# schematic.net
KiCad netlist of a schematic drawn in Altium Designer
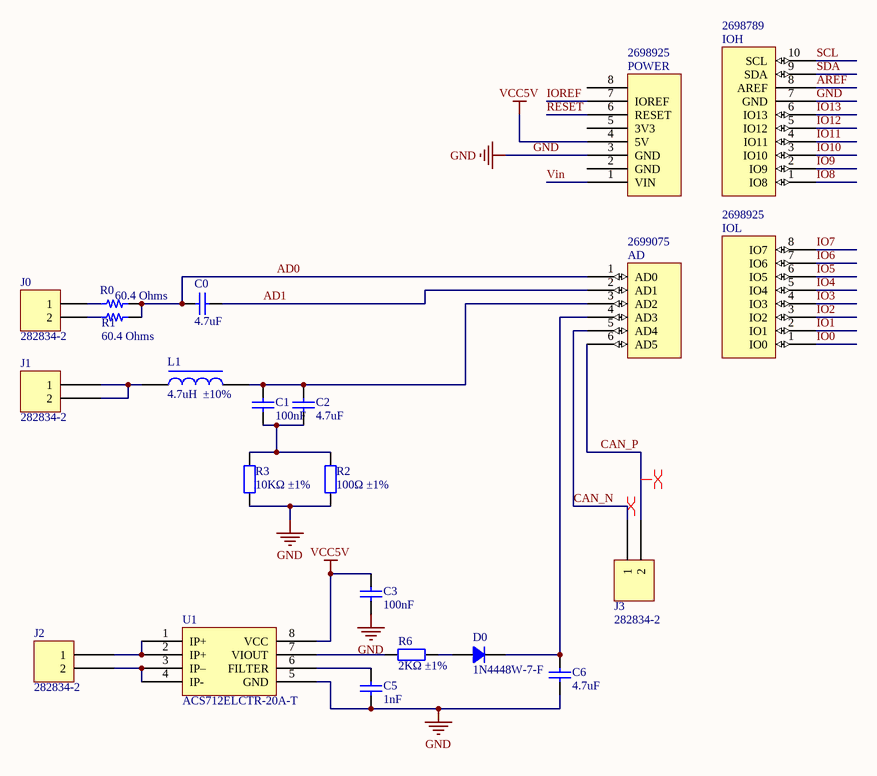
[diagram p0: schematic.SchDoc]

(export (version "E")
  (design (tool "Eeschema 10.0.6"))
  (components
    (comp (ref "AD")
      (value "AD")
      (footprint "Header:Header 6x1 8.5mm")
      (fields (field (name "SUPPLIER PART NUMBER 4") "2699075"))
      (libsource (lib "Header") (part "AD"))
    )
    (comp (ref "C0")
      (value "4.7uF")
      (footprint "1206_C")
      (description "Chip capacitors")
      (fields
        (field (name "MANUFACTURER") "Guangdong Fenghua Advanced Tech")
        (field (name "PARTNUMBER") "1206B475K500NT")
      )
      (libsource (lib "Cap") (part "1206 4.7uF (475) 10% 50V"))
    )
    (comp (ref "C1")
      (value "100nF")
      (footprint "0603_C")
      (description "Chip capacitors")
      (fields (field (name "MANUFACTURER") "YAGEO") (field (name "PARTNUMBER") "CC0603KRX7R9BB104"))
      (libsource (lib "Cap") (part "0603 100nF (104) 10% 50V"))
    )
    (comp (ref "C2")
      (value "4.7uF")
      (footprint "1206_C")
      (description "Chip capacitors")
      (fields
        (field (name "MANUFACTURER") "Guangdong Fenghua Advanced Tech")
        (field (name "PARTNUMBER") "1206B475K500NT")
      )
      (libsource (lib "Cap") (part "1206 4.7uF (475) 10% 50V"))
    )
    (comp (ref "C3")
      (value "100nF")
      (footprint "1206_C")
      (description "Chip capacitors")
      (fields
        (field (name "MANUFACTURER") "Samsung Electro-Mechanics")
        (field (name "PARTNUMBER") "CL31B104KBCNNNC")
      )
      (libsource (lib "Cap") (part "1206 100nF (104) 10% 50V"))
    )
    (comp (ref "C5")
      (value "1nF")
      (footprint "0402_C")
      (description "Chip capacitor")
      (fields
        (field (name "MANUFACTURER") "Guangdong Fenghua Advanced Tech")
        (field (name "PARTNUMBER") "0402B102K500NT")
      )
      (libsource (lib "Cap") (part "0402 1nF (102) 10% 50V"))
    )
    (comp (ref "C6")
      (value "4.7uF")
      (footprint "0402_C")
      (description "Chip capacitor")
      (fields
        (field (name "MANUFACTURER") "Samsung Electro-Mechanics")
        (field (name "PARTNUMBER") "CL05A475MP5NRNC")
      )
      (libsource (lib "Cap") (part "0402 4.7uF (475) 20% 10V"))
    )
    (comp (ref "D0")
      (value "1N4448W-7-F")
      (footprint "SOD-123")
      (description "DIODE GEN PURP 75V 250MA SOD123")
      (fields (field (name "MANUFACTURER") "Diodes Incorporated"))
      (libsource (lib "Celestial Altium Library - altium_library") (part "Diode"))
    )
    (comp (ref "IOH")
      (value "IOH")
      (footprint "Header:Header 10x1 8.5mm")
      (fields (field (name "SUPPLIER PART NUMBER 3") "2698789"))
      (libsource (lib "Header") (part "IOH"))
    )
    (comp (ref "IOL")
      (value "IOL")
      (footprint "Header 8x1 8.5mm")
      (fields (field (name "SUPPLIER PART NUMBER 4") "2698925"))
      (libsource (lib "Header") (part "IOL"))
    )
    (comp (ref "J0")
      (value "282834-2")
      (footprint "TE 282834-2")
      (description "TERM BLK 2P SIDE ENT 2.54MM PCB")
      (fields (field (name "MANUFACTURER") "TE Connectivity AMP Connectors") (field (name "VOLTAGE") "150V"))
      (libsource (lib "Celestial Altium Library - altium_library") (part "2 Pin"))
    )
    (comp (ref "J1")
      (value "282834-2")
      (footprint "TE 282834-2")
      (description "TERM BLK 2P SIDE ENT 2.54MM PCB")
      (fields (field (name "MANUFACTURER") "TE Connectivity AMP Connectors") (field (name "VOLTAGE") "150V"))
      (libsource (lib "Celestial Altium Library - altium_library") (part "2 Pin"))
    )
    (comp (ref "J2")
      (value "282834-2")
      (footprint "TE 282834-2")
      (description "TERM BLK 2P SIDE ENT 2.54MM PCB")
      (fields (field (name "MANUFACTURER") "TE Connectivity AMP Connectors") (field (name "VOLTAGE") "150V"))
      (libsource (lib "Celestial Altium Library - altium_library") (part "2 Pin"))
    )
    (comp (ref "J3")
      (value "282834-2")
      (footprint "TE 282834-2")
      (description "TERM BLK 2P SIDE ENT 2.54MM PCB")
      (fields (field (name "MANUFACTURER") "TE Connectivity AMP Connectors") (field (name "VOLTAGE") "150V"))
      (libsource (lib "") (part "2 Pin_1"))
    )
    (comp (ref "L1")
      (value "4.7uH  ±10%")
      (footprint "1206_L")
      (description "贴片电感")
      (libsource (lib "IUD") (part "1206 4.7uH  10%"))
    )
    (comp (ref "POWER")
      (value "POWER_UNO")
      (footprint "Header 8x1 8.5mm")
      (fields (field (name "SUPPLIER PART NUMBER 4") "2698925"))
      (libsource (lib "Header") (part "POWER_UNO"))
    )
    (comp (ref "R0")
      (value "60.4 Ohms")
      (footprint "RES 0805_2012")
      (description "RES 60.4 OHM 1% 1/8W 0805")
      (fields
        (field (name "PART NUMBER") "RMCF0805FT60R4")
        (field (name "MANUFACTURER") "Stackpole Electronics Inc")
      )
      (libsource (lib "Celestial Altium Library - altium_library") (part "Resistor"))
    )
    (comp (ref "R1")
      (value "60.4 Ohms")
      (footprint "RES 0805_2012")
      (description "RES 60.4 OHM 1% 1/8W 0805")
      (fields
        (field (name "PART NUMBER") "RMCF0805FT60R4")
        (field (name "MANUFACTURER") "Stackpole Electronics Inc")
      )
      (libsource (lib "Celestial Altium Library - altium_library") (part "Resistor"))
    )
    (comp (ref "R2")
      (value "100Ω ±1%")
      (footprint "1206_R")
      (description "Chip resistor")
      (fields (field (name "MANUFACTURER") "Uniroyal Elec") (field (name "POWER") "1/4W"))
      (libsource (lib "RES") (part "1206 100R (1000) 1%"))
    )
    (comp (ref "R3")
      (value "10KΩ ±1%")
      (footprint "1206_R")
      (description "Chip resistor")
      (fields (field (name "MANUFACTURER") "Uniroyal Elec") (field (name "POWER") "1/4W"))
      (libsource (lib "RES") (part "1206 10K (1002) 1%"))
    )
    (comp (ref "R6")
      (value "2KΩ ±1%")
      (footprint "0402_R")
      (description "Chip resistor")
      (fields (field (name "MANUFACTURER") "Uniroyal Elec") (field (name "PARTNUMBER") "0402WGF2001TCE"))
      (libsource (lib "RES") (part "0402 2K (2001) 1%"))
    )
    (comp (ref "U1")
      (value "ACS712ELCTR-20A-T")
      (footprint "SOIC-8_150mil")
      (description "传感器")
      (libsource (lib "Miscellaneous Devices LC") (part "ACS712ELCTR-20A-T_[C10681]"))
    )
  )
  (nets
    (net (code "2") (name "/AD0") (class "Default")
      (node (ref "AD") (pin "1") (pinfunction "AD0_1") (pintype "bidirectional"))
      (node (ref "C0") (pin "1") (pinfunction "1_1") (pintype "passive"))
      (node (ref "R0") (pin "1") (pinfunction "1_1") (pintype "passive"))
      (node (ref "R1") (pin "1") (pinfunction "1_1") (pintype "passive"))
    )
    (net (code "3") (name "/AD1") (class "Default")
      (node (ref "AD") (pin "2") (pinfunction "AD1_2") (pintype "bidirectional"))
      (node (ref "C0") (pin "2") (pinfunction "2_2") (pintype "passive"))
    )
    (net (code "4") (name "/AREF") (class "Default")
      (node (ref "IOH") (pin "8") (pinfunction "AREF_8") (pintype "passive"))
    )
    (net (code "5") (name "/CAN_N") (class "Default")
      (node (ref "AD") (pin "5") (pinfunction "AD4_5") (pintype "bidirectional"))
      (node (ref "J3") (pin "1") (pinfunction "1_1") (pintype "passive"))
    )
    (net (code "6") (name "/CAN_P") (class "Default")
      (node (ref "AD") (pin "6") (pinfunction "AD5_6") (pintype "bidirectional"))
      (node (ref "J3") (pin "2") (pinfunction "2_2") (pintype "passive"))
    )
    (net (code "7") (name "/IO0") (class "Default")
      (node (ref "IOL") (pin "1") (pinfunction "IO0_1") (pintype "bidirectional"))
    )
    (net (code "8") (name "/IO1") (class "Default")
      (node (ref "IOL") (pin "2") (pinfunction "IO1_2") (pintype "bidirectional"))
    )
    (net (code "9") (name "/IO2") (class "Default")
      (node (ref "IOL") (pin "3") (pinfunction "IO2_3") (pintype "bidirectional"))
    )
    (net (code "10") (name "/IO3") (class "Default")
      (node (ref "IOL") (pin "4") (pinfunction "IO3_4") (pintype "bidirectional"))
    )
    (net (code "11") (name "/IO4") (class "Default")
      (node (ref "IOL") (pin "5") (pinfunction "IO4_5") (pintype "bidirectional"))
    )
    (net (code "12") (name "/IO5") (class "Default")
      (node (ref "IOL") (pin "6") (pinfunction "IO5_6") (pintype "bidirectional"))
    )
    (net (code "13") (name "/IO6") (class "Default")
      (node (ref "IOL") (pin "7") (pinfunction "IO6_7") (pintype "bidirectional"))
    )
    (net (code "14") (name "/IO7") (class "Default")
      (node (ref "IOL") (pin "8") (pinfunction "IO7_8") (pintype "bidirectional"))
    )
    (net (code "15") (name "/IO8") (class "Default")
      (node (ref "IOH") (pin "1") (pinfunction "IO8_1") (pintype "bidirectional"))
    )
    (net (code "16") (name "/IO9") (class "Default")
      (node (ref "IOH") (pin "2") (pinfunction "IO9_2") (pintype "bidirectional"))
    )
    (net (code "17") (name "/IO10") (class "Default")
      (node (ref "IOH") (pin "3") (pinfunction "IO10_3") (pintype "bidirectional"))
    )
    (net (code "18") (name "/IO11") (class "Default")
      (node (ref "IOH") (pin "4") (pinfunction "IO11_4") (pintype "bidirectional"))
    )
    (net (code "19") (name "/IO12") (class "Default")
      (node (ref "IOH") (pin "5") (pinfunction "IO12_5") (pintype "bidirectional"))
    )
    (net (code "20") (name "/IO13") (class "Default")
      (node (ref "IOH") (pin "6") (pinfunction "IO13_6") (pintype "bidirectional"))
    )
    (net (code "21") (name "/IOREF") (class "Default")
      (node (ref "POWER") (pin "7") (pinfunction "IOREF_7") (pintype "power_in"))
    )
    (net (code "22") (name "/RESET") (class "Default")
      (node (ref "POWER") (pin "6") (pinfunction "RESET_6") (pintype "passive"))
    )
    (net (code "23") (name "/SCL") (class "Default")
      (node (ref "IOH") (pin "10") (pinfunction "SCL_10") (pintype "bidirectional"))
    )
    (net (code "24") (name "/SDA") (class "Default")
      (node (ref "IOH") (pin "9") (pinfunction "SDA_9") (pintype "bidirectional"))
    )
    (net (code "25") (name "/Vin") (class "Default")
      (node (ref "POWER") (pin "1") (pinfunction "VIN_1") (pintype "power_in"))
    )
    (net (code "26") (name "GND") (class "Default")
      (node (ref "C3") (pin "1") (pinfunction "1_1") (pintype "passive"))
      (node (ref "C5") (pin "1") (pinfunction "1_1") (pintype "passive"))
      (node (ref "C6") (pin "1") (pinfunction "1_1") (pintype "passive"))
      (node (ref "IOH") (pin "7") (pinfunction "GND_7") (pintype "power_in"))
      (node (ref "POWER") (pin "3") (pinfunction "GND_3") (pintype "power_in"))
      (node (ref "R2") (pin "1") (pinfunction "1_1") (pintype "passive"))
      (node (ref "R3") (pin "1") (pinfunction "1_1") (pintype "passive"))
      (node (ref "U1") (pin "5") (pinfunction "GND_5") (pintype "passive"))
    )
    (net (code "27") (name "Net-(AD-AD2)") (class "Default")
      (node (ref "AD") (pin "3") (pinfunction "AD2_3") (pintype "bidirectional"))
      (node (ref "C1") (pin "2") (pinfunction "2_2") (pintype "passive"))
      (node (ref "C2") (pin "1") (pinfunction "1_1") (pintype "passive"))
      (node (ref "L1") (pin "2") (pinfunction "2_2") (pintype "passive"))
    )
    (net (code "28") (name "Net-(AD-AD3)") (class "Default")
      (node (ref "AD") (pin "4") (pinfunction "AD3_4") (pintype "bidirectional"))
      (node (ref "C6") (pin "2") (pinfunction "2_2") (pintype "passive"))
      (node (ref "D0") (pin "2") (pinfunction "2_2") (pintype "passive"))
    )
    (net (code "29") (name "Net-(C1-Pad1)") (class "Default")
      (node (ref "C1") (pin "1") (pinfunction "1_1") (pintype "passive"))
      (node (ref "C2") (pin "2") (pinfunction "2_2") (pintype "passive"))
      (node (ref "R2") (pin "2") (pinfunction "2_2") (pintype "passive"))
      (node (ref "R3") (pin "2") (pinfunction "2_2") (pintype "passive"))
    )
    (net (code "30") (name "Net-(D0-Pad1)") (class "Default")
      (node (ref "D0") (pin "1") (pinfunction "1_1") (pintype "passive"))
      (node (ref "R6") (pin "2") (pinfunction "2_2") (pintype "passive"))
    )
    (net (code "31") (name "Net-(J0-Pad1)") (class "Default")
      (node (ref "J0") (pin "1") (pinfunction "1_1") (pintype "passive"))
      (node (ref "R0") (pin "2") (pinfunction "2_2") (pintype "passive"))
    )
    (net (code "32") (name "Net-(J0-Pad2)") (class "Default")
      (node (ref "J0") (pin "2") (pinfunction "2_2") (pintype "passive"))
      (node (ref "R1") (pin "2") (pinfunction "2_2") (pintype "passive"))
    )
    (net (code "33") (name "Net-(J1-Pad1)") (class "Default")
      (node (ref "J1") (pin "1") (pinfunction "1_1") (pintype "passive"))
      (node (ref "J1") (pin "2") (pinfunction "2_2") (pintype "passive"))
      (node (ref "L1") (pin "1") (pinfunction "1_1") (pintype "passive"))
    )
    (net (code "34") (name "Net-(J2-Pad1)") (class "Default")
      (node (ref "J2") (pin "1") (pinfunction "1_1") (pintype "passive"))
      (node (ref "U1") (pin "1") (pinfunction "IP+_1") (pintype "passive"))
      (node (ref "U1") (pin "2") (pinfunction "IP+_2") (pintype "passive"))
    )
    (net (code "35") (name "Net-(U1-FILTER)") (class "Default")
      (node (ref "C5") (pin "2") (pinfunction "2_2") (pintype "passive"))
      (node (ref "U1") (pin "6") (pinfunction "FILTER_6") (pintype "passive"))
    )
    (net (code "36") (name "Net-(U1-IP-)") (class "Default")
      (node (ref "J2") (pin "2") (pinfunction "2_2") (pintype "passive"))
      (node (ref "U1") (pin "3") (pinfunction "IP–_3") (pintype "passive"))
      (node (ref "U1") (pin "4") (pinfunction "IP-_4") (pintype "passive"))
    )
    (net (code "37") (name "Net-(U1-VIOUT)") (class "Default")
      (node (ref "R6") (pin "1") (pinfunction "1_1") (pintype "passive"))
      (node (ref "U1") (pin "7") (pinfunction "VIOUT_7") (pintype "passive"))
    )
    (net (code "38") (name "VCC5V") (class "Default")
      (node (ref "C3") (pin "2") (pinfunction "2_2") (pintype "passive"))
      (node (ref "POWER") (pin "4") (pinfunction "5V_4") (pintype "power_in"))
      (node (ref "U1") (pin "8") (pinfunction "VCC_8") (pintype "passive"))
    )
    (net (code "39") (name "unconnected-(POWER-3V3-Pad5)") (class "Default")
      (node (ref "POWER") (pin "5") (pinfunction "3V3_5") (pintype "power_in"))
    )
    (net (code "40") (name "unconnected-(POWER-GND-Pad2)") (class "Default")
      (node (ref "POWER") (pin "2") (pinfunction "GND_2") (pintype "power_in"))
    )
    (net (code "41") (name "unconnected-(POWER-Pad8)") (class "Default")
      (node (ref "POWER") (pin "8") (pintype "passive"))
    )
  )
)
